# VoltageSupervisor3_3V_5V.net
KiCad netlist of a schematic drawn in Altium Designer
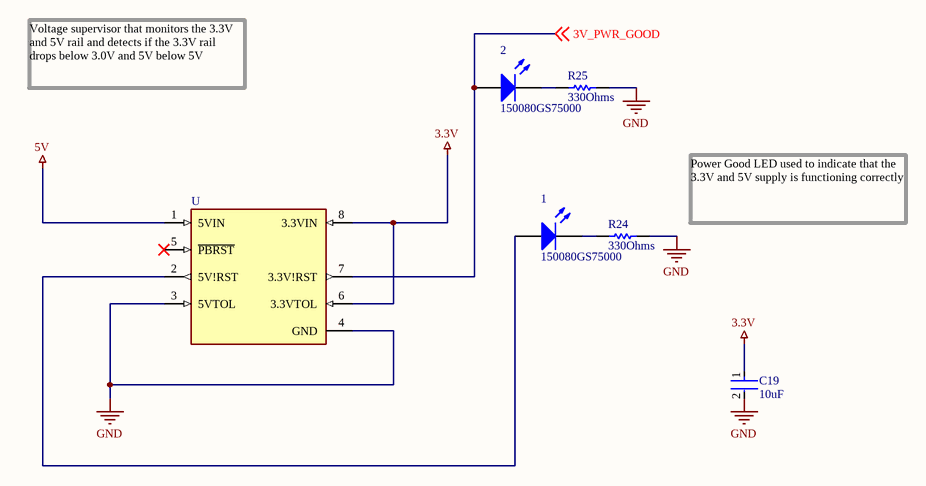
[diagram p0: VoltageSupervisor3.3V_5V.SchDoc]

(export (version "E")
  (design (tool "Eeschema 10.0.6"))
  (components
    (comp (ref "1")
      (value "150080GS75000")
      (footprint "0805_A")
      (description "SMD mono-color Chip LED, WL-SMCW, Green")
      (fields (field (name "MANUFACTURER") "Wuerth Elektronik"))
      (libsource (lib "Altium Content Vault") (part "WE-LED_K1A2-2"))
    )
    (comp (ref "2")
      (value "150080GS75000")
      (footprint "0805_A")
      (description "SMD mono-color Chip LED, WL-SMCW, Green")
      (fields (field (name "MANUFACTURER") "Wuerth Elektronik"))
      (libsource (lib "Altium Content Vault") (part "WE-LED_K1A2-2"))
    )
    (comp (ref "C19")
      (value "10uF")
      (footprint "FP-C0805C-DG-MFG")
      (description "CAP CER 10UF 10V X5R 0805")
      (fields (field (name "TOLERANCE") "10%") (field (name "MANUFACTURER PART NUMBER") "C0805C106K8PACTU"))
      (libsource (lib "Altium Content Vault") (part "11868f565c42a9108669ba33697ecf6"))
    )
    (comp (ref "R24")
      (value "RC0805FR-07330RL")
      (footprint "RESC2013X60X35LL10T20")
      (description "Chip Resistor, 330 Ohm, +/- 1%, 125 mW, -55 to 155 degC, 0805 (2012 Metric), RoHS, Tape and Reel")
      (fields
        (field (name "MANUFACTURER") "Yageo")
        (field (name "TOLERANCE") "1%")
        (field (name "RESISTANCE") "330Ohms")
      )
      (libsource (lib "Altium Content Vault") (part "RES-2"))
    )
    (comp (ref "R25")
      (value "RC0805FR-07330RL")
      (footprint "RESC2013X60X35LL10T20")
      (description "Chip Resistor, 330 Ohm, +/- 1%, 125 mW, -55 to 155 degC, 0805 (2012 Metric), RoHS, Tape and Reel")
      (fields
        (field (name "MANUFACTURER") "Yageo")
        (field (name "TOLERANCE") "1%")
        (field (name "RESISTANCE") "330Ohms")
      )
      (libsource (lib "Altium Content Vault") (part "RES-2"))
    )
    (comp (ref "U")
      (value "DS1834S+")
      (footprint "SnapEDApcb:SOIC127P600X175-8N")
      (description "Processor Supervisor 4.63V/2.88V 3.3V/5V 8-Pin SOIC N")
      (fields (field (name "MF") "Maxim Integrated") (field (name "MANUFACTURER") "Maxim"))
      (libsource (lib "SnapEDAsch") (part "DS1834S+"))
    )
  )
  (nets
    (net (code "1") (name "3.3V") (class "Default")
      (node (ref "C19") (pin "1") (pinfunction "1_1") (pintype "passive"))
      (node (ref "U") (pin "6") (pinfunction "3.3VTOL_6") (pintype "input"))
      (node (ref "U") (pin "8") (pinfunction "3.3VIN_8") (pintype "input"))
    )
    (net (code "2") (name "3V_PWR_GOOD") (class "Default")
      (node (ref "2") (pin "2") (pinfunction "A_2") (pintype "passive"))
      (node (ref "U") (pin "7") (pinfunction "3.3V!RST_7") (pintype "output"))
    )
    (net (code "3") (name "5V") (class "Default")
      (node (ref "U") (pin "1") (pinfunction "5VIN_1") (pintype "input"))
    )
    (net (code "4") (name "GND") (class "Default")
      (node (ref "C19") (pin "2") (pinfunction "2_2") (pintype "passive"))
      (node (ref "R24") (pin "1") (pinfunction "1_1") (pintype "passive"))
      (node (ref "R25") (pin "1") (pinfunction "1_1") (pintype "passive"))
      (node (ref "U") (pin "3") (pinfunction "5VTOL_3") (pintype "input"))
      (node (ref "U") (pin "4") (pinfunction "GND_4") (pintype "power_in"))
    )
    (net (code "5") (name "Net-(1-A)") (class "Default")
      (node (ref "1") (pin "2") (pinfunction "A_2") (pintype "passive"))
      (node (ref "U") (pin "2") (pinfunction "5V!RST_2") (pintype "output"))
    )
    (net (code "6") (name "Net-(1-K)") (class "Default")
      (node (ref "1") (pin "1") (pinfunction "K_1") (pintype "passive"))
      (node (ref "R24") (pin "2") (pinfunction "2_2") (pintype "passive"))
    )
    (net (code "7") (name "Net-(2-K)") (class "Default")
      (node (ref "2") (pin "1") (pinfunction "K_1") (pintype "passive"))
      (node (ref "R25") (pin "2") (pinfunction "2_2") (pintype "passive"))
    )
    (net (code "8") (name "unconnected-(U-~{PBRST}-Pad5)") (class "Default")
      (node (ref "U") (pin "5") (pinfunction "~{PBRST}_5") (pintype "input+no_connect"))
    )
  )
)
